# FTDI.net
KiCad netlist of a schematic drawn in Altium Designer
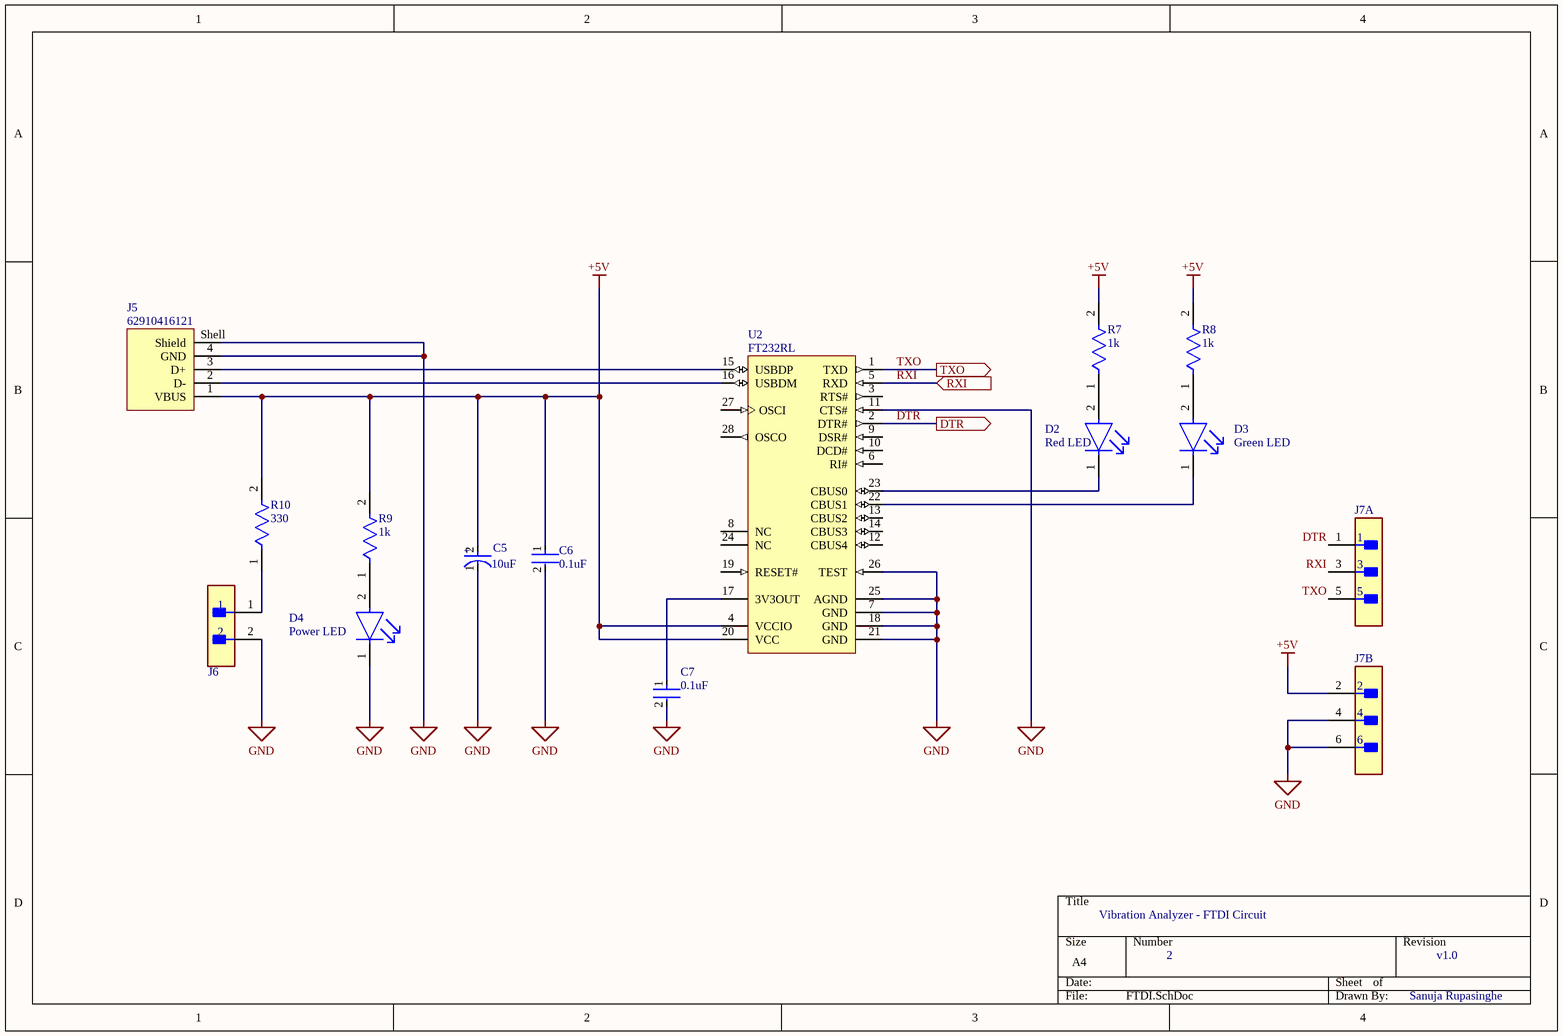
[diagram p0: FTDI.SchDoc]

(export (version "E")
  (design (tool "Eeschema 10.0.6"))
  (components
    (comp (ref "C5")
      (value "EEE1VA100SR")
      (footprint "FP-SC-MFG")
      (description "CAP ALUM 10UF 20% 35V SMD")
      (fields
        (field (name "CAPACITANCE") "10uF")
        (field (name "TOLERANCE") "20%")
        (field (name "VOLTAGE") "35V")
      )
      (libsource (lib "Altium Content Vault") (part "203bc49f2ac43e59fd269a8c329ed05"))
    )
    (comp (ref "C6")
      (value "GRM31M1X1H104JA01L")
      (footprint "FP-GRM31M-0_15-IPC_A")
      (fields
        (field (name "VOLTAGE") "50V")
        (field (name "TOLERANCE") "5%")
        (field (name "CAPACITANCE") "0.1uF")
      )
      (libsource (lib "Altium Content Vault") (part "b4654b650e69147ec39a6b967a45e02"))
    )
    (comp (ref "C7")
      (value "GRM31M1X1H104JA01L")
      (footprint "FP-GRM31M-0_15-IPC_A")
      (fields
        (field (name "VOLTAGE") "50V")
        (field (name "TOLERANCE") "5%")
        (field (name "CAPACITANCE") "0.1uF")
      )
      (libsource (lib "Altium Content Vault") (part "b4654b650e69147ec39a6b967a45e02"))
    )
    (comp (ref "D2")
      (value "HSMG-C150")
      (footprint "FP-HSMG-C150-MFG")
      (description "LED GREEN DIFFUSED 1206 SMD")
      (fields
        (field (name "MANUFACTURER") "Broadcom")
        (field (name "OCTOPART") "https://octopart.com/hsmg-c150-broadcom-71131304")
        (field (name "COLOR") "Red LED")
      )
      (libsource (lib "Altium Content Vault") (part "8706943c75ba83719d021d2fdc84c58"))
    )
    (comp (ref "D3")
      (value "HSMG-C150")
      (footprint "FP-HSMG-C150-MFG")
      (description "LED GREEN DIFFUSED 1206 SMD")
      (fields
        (field (name "MANUFACTURER") "Broadcom")
        (field (name "OCTOPART") "https://octopart.com/hsmg-c150-broadcom-71131304")
        (field (name "COLOR") "Green LED")
      )
      (libsource (lib "Altium Content Vault") (part "8706943c75ba83719d021d2fdc84c58"))
    )
    (comp (ref "D4")
      (value "HSMG-C150")
      (footprint "FP-HSMG-C150-MFG")
      (description "LED GREEN DIFFUSED 1206 SMD")
      (fields
        (field (name "MANUFACTURER") "Broadcom")
        (field (name "OCTOPART") "https://octopart.com/hsmg-c150-broadcom-71131304")
        (field (name "COLOR") "Power LED")
      )
      (libsource (lib "Altium Content Vault") (part "8706943c75ba83719d021d2fdc84c58"))
    )
    (comp (ref "J5")
      (value "62910416121")
      (footprint "62910416121")
      (libsource (lib "Altium Content Vault") (part "USB 2.0_Type B_Receptacle_1 Port"))
    )
    (comp (ref "J6")
      (value "B2B-XH-A(LF)(SN)")
      (footprint "FP-B2B-XH-A_LF_SN-MFG")
      (description "CONN HEADER VERT 2POS 2.5MM")
      (libsource (lib "Altium Content Vault") (part "3bc925449376181038e59eaffc5286c"))
    )
    (comp (ref "J7")
      (value "M20-9980346")
      (footprint "FP-M20-9980346-MFG")
      (description "2.54mm Pitch 6 Way 2 Row Straight PCB Header, Solder Termination, 3A")
      (fields (field (name "MANUFACTURER") "Harwin"))
      (libsource (lib "Altium Content Vault") (part "2654a11fb13586ecb194516b1c997bc"))
    )
    (comp (ref "R7")
      (value "MCR18EZPF30R0")
      (footprint "FP-MCR18-IPC_B")
      (description "Thick Film Chip Resistor, 1206, 30Ω, 1%, 100ppm/°C, 0.25W, 200V")
      (fields (field (name "RESISTANCE") "1k") (field (name "TOLERANCE") "1%"))
      (libsource (lib "Altium Content Vault") (part "1029c3af85768c4190bb7ad29bc67b5"))
    )
    (comp (ref "R8")
      (value "MCR18EZPF30R0")
      (footprint "FP-MCR18-IPC_B")
      (description "Thick Film Chip Resistor, 1206, 30Ω, 1%, 100ppm/°C, 0.25W, 200V")
      (fields (field (name "RESISTANCE") "1k") (field (name "TOLERANCE") "1%"))
      (libsource (lib "Altium Content Vault") (part "1029c3af85768c4190bb7ad29bc67b5"))
    )
    (comp (ref "R9")
      (value "MCR18EZPF30R0")
      (footprint "FP-MCR18-IPC_B")
      (description "Thick Film Chip Resistor, 1206, 30Ω, 1%, 100ppm/°C, 0.25W, 200V")
      (fields (field (name "RESISTANCE") "1k") (field (name "TOLERANCE") "1%"))
      (libsource (lib "Altium Content Vault") (part "1029c3af85768c4190bb7ad29bc67b5"))
    )
    (comp (ref "R10")
      (value "MCR18EZPF30R0")
      (footprint "FP-MCR18-IPC_B")
      (description "Thick Film Chip Resistor, 1206, 30Ω, 1%, 100ppm/°C, 0.25W, 200V")
      (fields (field (name "RESISTANCE") "330") (field (name "TOLERANCE") "1%"))
      (libsource (lib "Altium Content Vault") (part "1029c3af85768c4190bb7ad29bc67b5"))
    )
    (comp (ref "U2")
      (value "FT232RL")
      (footprint "FTDI-SSOP-28_M")
      (description "IC USB FS SERIAL UART 28-SSOP")
      (fields (field (name "MANUFACTURER") "FTDI"))
      (libsource (lib "Altium Content Vault") (part "FTDI-FT232-SSOP-28"))
    )
  )
  (nets
    (net (code "1") (name "+5V") (class "Default")
      (node (ref "C5") (pin "2") (pinfunction "A_2") (pintype "passive"))
      (node (ref "C6") (pin "1") (pinfunction "1_1") (pintype "passive"))
      (node (ref "J5") (pin "1") (pinfunction "VBUS_1") (pintype "passive"))
      (node (ref "J7") (pin "2") (pinfunction "2_2") (pintype "passive"))
      (node (ref "R10") (pin "2") (pinfunction "2_2") (pintype "passive"))
      (node (ref "R7") (pin "2") (pinfunction "2_2") (pintype "passive"))
      (node (ref "R8") (pin "2") (pinfunction "2_2") (pintype "passive"))
      (node (ref "R9") (pin "2") (pinfunction "2_2") (pintype "passive"))
      (node (ref "U2") (pin "20") (pinfunction "VCC_20") (pintype "power_in"))
      (node (ref "U2") (pin "4") (pinfunction "VCCIO_4") (pintype "power_in"))
    )
    (net (code "2") (name "/DTR") (class "Default")
      (node (ref "J7") (pin "1") (pinfunction "1_1") (pintype "passive"))
      (node (ref "U2") (pin "2") (pinfunction "DTR#_2") (pintype "output"))
    )
    (net (code "3") (name "/RXI") (class "Default")
      (node (ref "J7") (pin "3") (pinfunction "3_3") (pintype "passive"))
      (node (ref "U2") (pin "5") (pinfunction "RXD_5") (pintype "input"))
    )
    (net (code "4") (name "/TXO") (class "Default")
      (node (ref "J7") (pin "5") (pinfunction "5_5") (pintype "passive"))
      (node (ref "U2") (pin "1") (pinfunction "TXD_1") (pintype "output"))
    )
    (net (code "5") (name "GND") (class "Default")
      (node (ref "C5") (pin "1") (pinfunction "C_1") (pintype "passive"))
      (node (ref "C6") (pin "2") (pinfunction "2_2") (pintype "passive"))
      (node (ref "C7") (pin "2") (pinfunction "2_2") (pintype "passive"))
      (node (ref "D4") (pin "1") (pinfunction "C_1") (pintype "passive"))
      (node (ref "J5") (pin "4") (pinfunction "GND_4") (pintype "passive"))
      (node (ref "J5") (pin "Shell") (pinfunction "Shield_Shell") (pintype "passive"))
      (node (ref "J6") (pin "2") (pinfunction "2_2") (pintype "passive"))
      (node (ref "J7") (pin "4") (pinfunction "4_4") (pintype "passive"))
      (node (ref "J7") (pin "6") (pinfunction "6_6") (pintype "passive"))
      (node (ref "U2") (pin "11") (pinfunction "CTS#_11") (pintype "input"))
      (node (ref "U2") (pin "18") (pinfunction "GND_18") (pintype "power_in"))
      (node (ref "U2") (pin "21") (pinfunction "GND_21") (pintype "power_in"))
      (node (ref "U2") (pin "25") (pinfunction "AGND_25") (pintype "power_in"))
      (node (ref "U2") (pin "26") (pinfunction "TEST_26") (pintype "input"))
      (node (ref "U2") (pin "7") (pinfunction "GND_7") (pintype "power_in"))
    )
    (net (code "6") (name "Net-(D2-A)") (class "Default")
      (node (ref "D2") (pin "2") (pinfunction "A_2") (pintype "passive"))
      (node (ref "R7") (pin "1") (pinfunction "1_1") (pintype "passive"))
    )
    (net (code "7") (name "Net-(D2-C)") (class "Default")
      (node (ref "D2") (pin "1") (pinfunction "C_1") (pintype "passive"))
      (node (ref "U2") (pin "23") (pinfunction "CBUS0_23") (pintype "bidirectional"))
    )
    (net (code "8") (name "Net-(D3-A)") (class "Default")
      (node (ref "D3") (pin "2") (pinfunction "A_2") (pintype "passive"))
      (node (ref "R8") (pin "1") (pinfunction "1_1") (pintype "passive"))
    )
    (net (code "9") (name "Net-(D3-C)") (class "Default")
      (node (ref "D3") (pin "1") (pinfunction "C_1") (pintype "passive"))
      (node (ref "U2") (pin "22") (pinfunction "CBUS1_22") (pintype "bidirectional"))
    )
    (net (code "10") (name "Net-(D4-A)") (class "Default")
      (node (ref "D4") (pin "2") (pinfunction "A_2") (pintype "passive"))
      (node (ref "R9") (pin "1") (pinfunction "1_1") (pintype "passive"))
    )
    (net (code "11") (name "Net-(J5-D+)") (class "Default")
      (node (ref "J5") (pin "3") (pinfunction "D+_3") (pintype "passive"))
      (node (ref "U2") (pin "15") (pinfunction "USBDP_15") (pintype "bidirectional"))
    )
    (net (code "12") (name "Net-(J5-D-)") (class "Default")
      (node (ref "J5") (pin "2") (pinfunction "D-_2") (pintype "passive"))
      (node (ref "U2") (pin "16") (pinfunction "USBDM_16") (pintype "bidirectional"))
    )
    (net (code "13") (name "Net-(J6-Pad1)") (class "Default")
      (node (ref "J6") (pin "1") (pinfunction "1_1") (pintype "passive"))
      (node (ref "R10") (pin "1") (pinfunction "1_1") (pintype "passive"))
    )
    (net (code "14") (name "Net-(U2-3V3OUT)") (class "Default")
      (node (ref "C7") (pin "1") (pinfunction "1_1") (pintype "passive"))
      (node (ref "U2") (pin "17") (pinfunction "3V3OUT_17") (pintype "power_in"))
    )
    (net (code "15") (name "unconnected-(U2-CBUS2-Pad13)") (class "Default")
      (node (ref "U2") (pin "13") (pinfunction "CBUS2_13") (pintype "bidirectional"))
    )
    (net (code "16") (name "unconnected-(U2-CBUS3-Pad14)") (class "Default")
      (node (ref "U2") (pin "14") (pinfunction "CBUS3_14") (pintype "bidirectional"))
    )
    (net (code "17") (name "unconnected-(U2-CBUS4-Pad12)") (class "Default")
      (node (ref "U2") (pin "12") (pinfunction "CBUS4_12") (pintype "bidirectional"))
    )
    (net (code "18") (name "unconnected-(U2-DCD#-Pad10)") (class "Default")
      (node (ref "U2") (pin "10") (pinfunction "DCD#_10") (pintype "input"))
    )
    (net (code "19") (name "unconnected-(U2-DSR#-Pad9)") (class "Default")
      (node (ref "U2") (pin "9") (pinfunction "DSR#_9") (pintype "input"))
    )
    (net (code "20") (name "unconnected-(U2-NC-Pad8)") (class "Default")
      (node (ref "U2") (pin "8") (pinfunction "NC_8") (pintype "passive"))
    )
    (net (code "21") (name "unconnected-(U2-NC-Pad24)") (class "Default")
      (node (ref "U2") (pin "24") (pinfunction "NC_24") (pintype "passive"))
    )
    (net (code "22") (name "unconnected-(U2-OSCI-Pad27)") (class "Default")
      (node (ref "U2") (pin "27") (pinfunction "OSCI_27") (pintype "input"))
    )
    (net (code "23") (name "unconnected-(U2-OSCO-Pad28)") (class "Default")
      (node (ref "U2") (pin "28") (pinfunction "OSCO_28") (pintype "output"))
    )
    (net (code "24") (name "unconnected-(U2-RESET#-Pad19)") (class "Default")
      (node (ref "U2") (pin "19") (pinfunction "RESET#_19") (pintype "input"))
    )
    (net (code "25") (name "unconnected-(U2-RI#-Pad6)") (class "Default")
      (node (ref "U2") (pin "6") (pinfunction "RI#_6") (pintype "input"))
    )
    (net (code "26") (name "unconnected-(U2-RTS#-Pad3)") (class "Default")
      (node (ref "U2") (pin "3") (pinfunction "RTS#_3") (pintype "output"))
    )
  )
)
